# Filter_Circuit.net
KiCad netlist of a schematic drawn in EAGLE
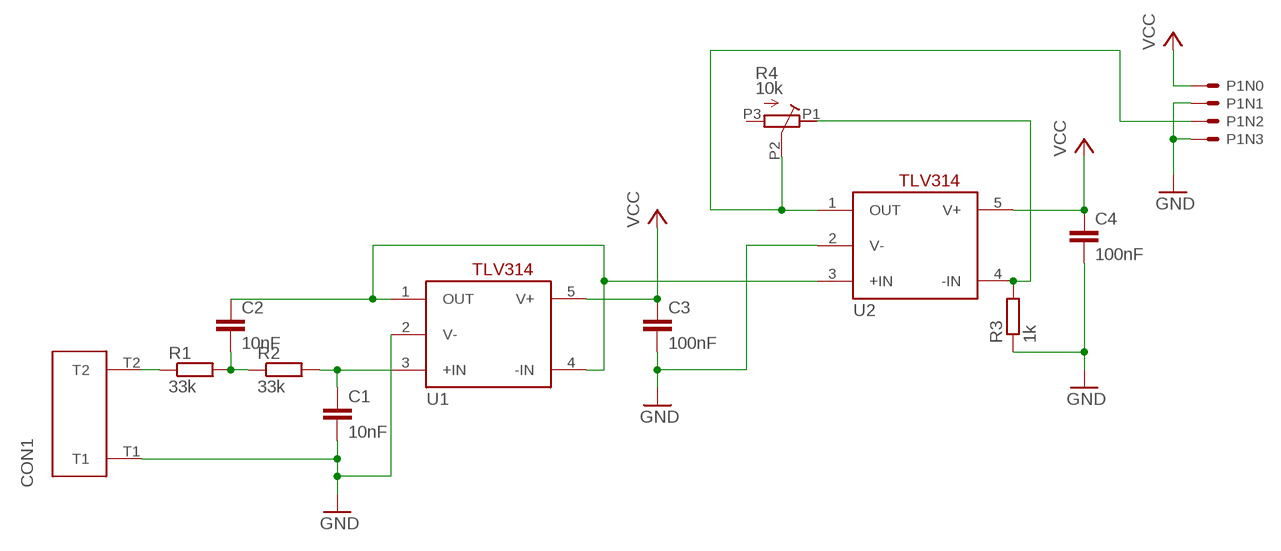
[diagram p0: schematic, sheet 1]

(export (version "E")
  (design (tool "Eeschema 10.0.6"))
  (components
    (comp (ref "C1")
      (value "10nF")
      (footprint "eagle-import:C1206")
      (libsource (lib "eagle-import") (part "C-EUC1206"))
    )
    (comp (ref "C2")
      (value "10nF")
      (footprint "eagle-import:C1206")
      (libsource (lib "eagle-import") (part "C-EUC1206"))
    )
    (comp (ref "C3")
      (value "100nF")
      (footprint "eagle-import:C1206")
      (libsource (lib "eagle-import") (part "C-EUC1206"))
    )
    (comp (ref "C4")
      (value "100nF")
      (footprint "eagle-import:C1206")
      (libsource (lib "eagle-import") (part "C-EUC1206"))
    )
    (comp (ref "CON1")
      (value "2PIN_SCREW_TERM")
      (footprint "eagle-import:2PIN_SCREW_TERM")
      (libsource (lib "eagle-import") (part "2PIN_SCREW_TERM"))
    )
    (comp (ref "P1")
      (value "4PINHEADER")
      (footprint "eagle-import:4PINHEADER")
      (libsource (lib "eagle-import") (part "4PINHEADER"))
    )
    (comp (ref "R1")
      (value "33k")
      (footprint "eagle-import:R1206")
      (libsource (lib "eagle-import") (part "R-EU_R1206"))
    )
    (comp (ref "R2")
      (value "33k")
      (footprint "eagle-import:R1206")
      (libsource (lib "eagle-import") (part "R-EU_R1206"))
    )
    (comp (ref "R3")
      (value "1k")
      (footprint "eagle-import:R1206")
      (libsource (lib "eagle-import") (part "R-EU_R1206"))
    )
    (comp (ref "R4")
      (value "10k")
      (footprint "eagle-import:POT_RESISTOR_SMD")
      (libsource (lib "eagle-import") (part "POT_RESISTOR_SMD"))
    )
    (comp (ref "U1")
      (value "TLV314_OP_AMP")
      (footprint "eagle-import:SOT23")
      (libsource (lib "eagle-import") (part "TLV314_OP_AMP"))
    )
    (comp (ref "U2")
      (value "TLV314_OP_AMP")
      (footprint "eagle-import:SOT23")
      (libsource (lib "eagle-import") (part "TLV314_OP_AMP"))
    )
  )
  (nets
    (net (code "1") (name "GND") (class "Default")
      (node (ref "C1") (pin "2") (pinfunction "2_2") (pintype "passive"))
      (node (ref "C3") (pin "2") (pinfunction "2_2") (pintype "passive"))
      (node (ref "C4") (pin "2") (pinfunction "2_2") (pintype "passive"))
      (node (ref "CON1") (pin "T1") (pinfunction "T1_T1") (pintype "bidirectional"))
      (node (ref "P1") (pin "N1") (pinfunction "S_N1") (pintype "passive"))
      (node (ref "P1") (pin "N3") (pinfunction "S_N3") (pintype "passive"))
      (node (ref "R3") (pin "1") (pinfunction "1_1") (pintype "passive"))
      (node (ref "U1") (pin "2") (pinfunction "V-_2") (pintype "bidirectional"))
      (node (ref "U2") (pin "2") (pinfunction "V-_2") (pintype "bidirectional"))
    )
    (net (code "2") (name "Net-(C2-Pad2)") (class "Default")
      (node (ref "C2") (pin "2") (pinfunction "2_2") (pintype "passive"))
      (node (ref "R1") (pin "2") (pinfunction "2_2") (pintype "passive"))
      (node (ref "R2") (pin "1") (pinfunction "1_1") (pintype "passive"))
    )
    (net (code "3") (name "Net-(CON1-PadT2)") (class "Default")
      (node (ref "CON1") (pin "T2") (pinfunction "T2_T2") (pintype "bidirectional"))
      (node (ref "R1") (pin "1") (pinfunction "1_1") (pintype "passive"))
    )
    (net (code "4") (name "Net-(P1C-S)") (class "Default")
      (node (ref "P1") (pin "N2") (pinfunction "S_N2") (pintype "passive"))
      (node (ref "R4") (pin "P2") (pinfunction "P2_P2") (pintype "passive"))
      (node (ref "U2") (pin "1") (pinfunction "OUT_1") (pintype "power_in"))
    )
    (net (code "5") (name "Net-(U1-+IN)") (class "Default")
      (node (ref "C1") (pin "1") (pinfunction "1_1") (pintype "passive"))
      (node (ref "R2") (pin "2") (pinfunction "2_2") (pintype "passive"))
      (node (ref "U1") (pin "3") (pinfunction "+IN_3") (pintype "bidirectional"))
    )
    (net (code "6") (name "Net-(U1--IN)") (class "Default")
      (node (ref "C2") (pin "1") (pinfunction "1_1") (pintype "passive"))
      (node (ref "U1") (pin "1") (pinfunction "OUT_1") (pintype "power_in"))
      (node (ref "U1") (pin "4") (pinfunction "-IN_4") (pintype "bidirectional"))
      (node (ref "U2") (pin "3") (pinfunction "+IN_3") (pintype "bidirectional"))
    )
    (net (code "7") (name "Net-(U2--IN)") (class "Default")
      (node (ref "R3") (pin "2") (pinfunction "2_2") (pintype "passive"))
      (node (ref "R4") (pin "P1") (pinfunction "P1_P1") (pintype "passive"))
      (node (ref "U2") (pin "4") (pinfunction "-IN_4") (pintype "bidirectional"))
    )
    (net (code "8") (name "VCC") (class "Default")
      (node (ref "C3") (pin "1") (pinfunction "1_1") (pintype "passive"))
      (node (ref "C4") (pin "1") (pinfunction "1_1") (pintype "passive"))
      (node (ref "P1") (pin "N0") (pinfunction "S_N0") (pintype "passive"))
      (node (ref "U1") (pin "5") (pinfunction "V+_5") (pintype "power_in"))
      (node (ref "U2") (pin "5") (pinfunction "V+_5") (pintype "power_in"))
    )
    (net (code "9") (name "unconnected-(R4-PadP3)") (class "Default")
      (node (ref "R4") (pin "P3") (pinfunction "P3_P3") (pintype "passive"))
    )
  )
)
